# Sheet1.net
KiCad netlist of a schematic drawn in Altium Designer
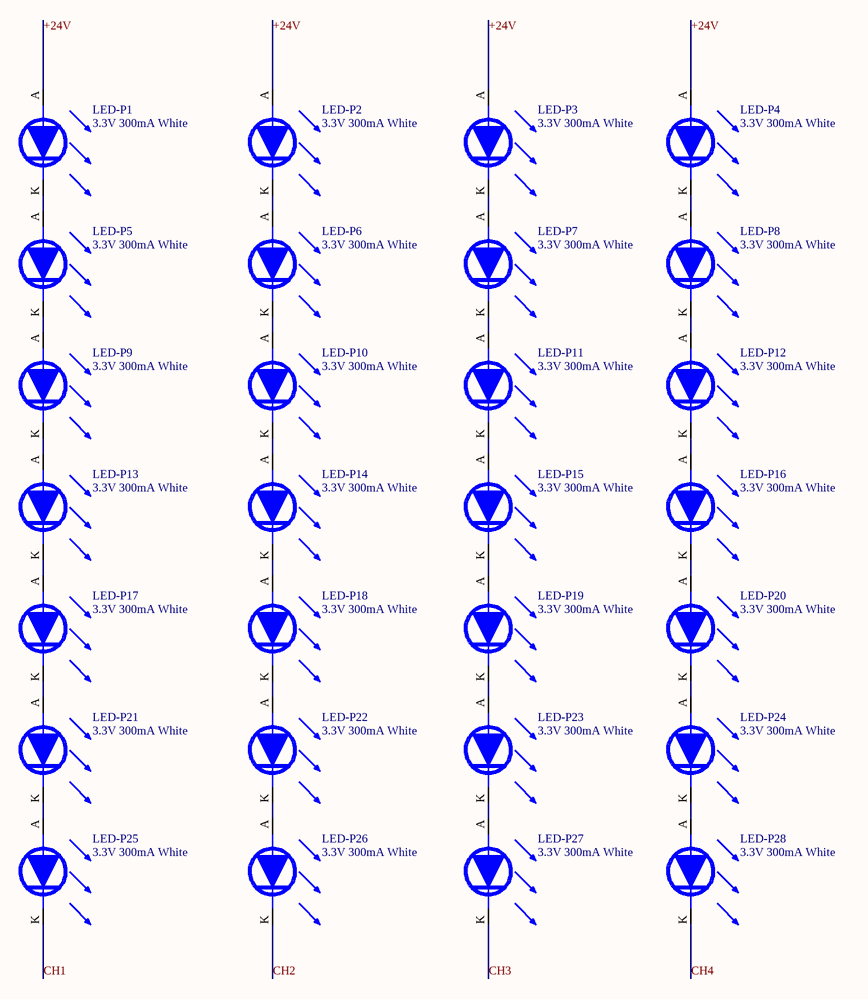
[diagram p0: Sheet1.SchDoc]

(export (version "E")
  (design (tool "Eeschema 10.0.6"))
  (components
    (comp (ref "LED-P1")
      (value "3.3V 300mA White")
      (footprint "PCBComponent_1")
      (description "High power 1W light emitting diode White")
      (libsource (lib "Integrated_Library1") (part "LED white P1"))
    )
    (comp (ref "LED-P2")
      (value "3.3V 300mA White")
      (footprint "PCBComponent_1")
      (description "High power 1W light emitting diode White")
      (libsource (lib "Integrated_Library1") (part "LED white P1"))
    )
    (comp (ref "LED-P3")
      (value "3.3V 300mA White")
      (footprint "PCBComponent_1")
      (description "High power 1W light emitting diode White")
      (libsource (lib "Integrated_Library1") (part "LED white P1"))
    )
    (comp (ref "LED-P4")
      (value "3.3V 300mA White")
      (footprint "PCBComponent_1")
      (description "High power 1W light emitting diode White")
      (libsource (lib "Integrated_Library1") (part "LED white P1"))
    )
    (comp (ref "LED-P5")
      (value "3.3V 300mA White")
      (footprint "PCBComponent_1")
      (description "High power 1W light emitting diode White")
      (libsource (lib "Integrated_Library1") (part "LED white P1"))
    )
    (comp (ref "LED-P6")
      (value "3.3V 300mA White")
      (footprint "PCBComponent_1")
      (description "High power 1W light emitting diode White")
      (libsource (lib "Integrated_Library1") (part "LED white P1"))
    )
    (comp (ref "LED-P7")
      (value "3.3V 300mA White")
      (footprint "PCBComponent_1")
      (description "High power 1W light emitting diode White")
      (libsource (lib "Integrated_Library1") (part "LED white P1"))
    )
    (comp (ref "LED-P8")
      (value "3.3V 300mA White")
      (footprint "PCBComponent_1")
      (description "High power 1W light emitting diode White")
      (libsource (lib "Integrated_Library1") (part "LED white P1"))
    )
    (comp (ref "LED-P9")
      (value "3.3V 300mA White")
      (footprint "PCBComponent_1")
      (description "High power 1W light emitting diode White")
      (libsource (lib "Integrated_Library1") (part "LED white P1"))
    )
    (comp (ref "LED-P10")
      (value "3.3V 300mA White")
      (footprint "PCBComponent_1")
      (description "High power 1W light emitting diode White")
      (libsource (lib "Integrated_Library1") (part "LED white P1"))
    )
    (comp (ref "LED-P11")
      (value "3.3V 300mA White")
      (footprint "PCBComponent_1")
      (description "High power 1W light emitting diode White")
      (libsource (lib "Integrated_Library1") (part "LED white P1"))
    )
    (comp (ref "LED-P12")
      (value "3.3V 300mA White")
      (footprint "PCBComponent_1")
      (description "High power 1W light emitting diode White")
      (libsource (lib "Integrated_Library1") (part "LED white P1"))
    )
    (comp (ref "LED-P13")
      (value "3.3V 300mA White")
      (footprint "PCBComponent_1")
      (description "High power 1W light emitting diode White")
      (libsource (lib "Integrated_Library1") (part "LED white P1"))
    )
    (comp (ref "LED-P14")
      (value "3.3V 300mA White")
      (footprint "PCBComponent_1")
      (description "High power 1W light emitting diode White")
      (libsource (lib "Integrated_Library1") (part "LED white P1"))
    )
    (comp (ref "LED-P15")
      (value "3.3V 300mA White")
      (footprint "PCBComponent_1")
      (description "High power 1W light emitting diode White")
      (libsource (lib "Integrated_Library1") (part "LED white P1"))
    )
    (comp (ref "LED-P16")
      (value "3.3V 300mA White")
      (footprint "PCBComponent_1")
      (description "High power 1W light emitting diode White")
      (libsource (lib "Integrated_Library1") (part "LED white P1"))
    )
    (comp (ref "LED-P17")
      (value "3.3V 300mA White")
      (footprint "PCBComponent_1")
      (description "High power 1W light emitting diode White")
      (libsource (lib "Integrated_Library1") (part "LED white P1"))
    )
    (comp (ref "LED-P18")
      (value "3.3V 300mA White")
      (footprint "PCBComponent_1")
      (description "High power 1W light emitting diode White")
      (libsource (lib "Integrated_Library1") (part "LED white P1"))
    )
    (comp (ref "LED-P19")
      (value "3.3V 300mA White")
      (footprint "PCBComponent_1")
      (description "High power 1W light emitting diode White")
      (libsource (lib "Integrated_Library1") (part "LED white P1"))
    )
    (comp (ref "LED-P20")
      (value "3.3V 300mA White")
      (footprint "PCBComponent_1")
      (description "High power 1W light emitting diode White")
      (libsource (lib "Integrated_Library1") (part "LED white P1"))
    )
    (comp (ref "LED-P21")
      (value "3.3V 300mA White")
      (footprint "PCBComponent_1")
      (description "High power 1W light emitting diode White")
      (libsource (lib "Integrated_Library1") (part "LED white P1"))
    )
    (comp (ref "LED-P22")
      (value "3.3V 300mA White")
      (footprint "PCBComponent_1")
      (description "High power 1W light emitting diode White")
      (libsource (lib "Integrated_Library1") (part "LED white P1"))
    )
    (comp (ref "LED-P23")
      (value "3.3V 300mA White")
      (footprint "PCBComponent_1")
      (description "High power 1W light emitting diode White")
      (libsource (lib "Integrated_Library1") (part "LED white P1"))
    )
    (comp (ref "LED-P24")
      (value "3.3V 300mA White")
      (footprint "PCBComponent_1")
      (description "High power 1W light emitting diode White")
      (libsource (lib "Integrated_Library1") (part "LED white P1"))
    )
    (comp (ref "LED-P25")
      (value "3.3V 300mA White")
      (footprint "PCBComponent_1")
      (description "High power 1W light emitting diode White")
      (libsource (lib "Integrated_Library1") (part "LED white P1"))
    )
    (comp (ref "LED-P26")
      (value "3.3V 300mA White")
      (footprint "PCBComponent_1")
      (description "High power 1W light emitting diode White")
      (libsource (lib "Integrated_Library1") (part "LED white P1"))
    )
    (comp (ref "LED-P27")
      (value "3.3V 300mA White")
      (footprint "PCBComponent_1")
      (description "High power 1W light emitting diode White")
      (libsource (lib "Integrated_Library1") (part "LED white P1"))
    )
    (comp (ref "LED-P28")
      (value "3.3V 300mA White")
      (footprint "PCBComponent_1")
      (description "High power 1W light emitting diode White")
      (libsource (lib "Integrated_Library1") (part "LED white P1"))
    )
  )
  (nets
    (net (code "1") (name "/+24V") (class "Default")
      (node (ref "LED-P1") (pin "A") (pinfunction "A_A") (pintype "passive"))
      (node (ref "LED-P2") (pin "A") (pinfunction "A_A") (pintype "passive"))
      (node (ref "LED-P3") (pin "A") (pinfunction "A_A") (pintype "passive"))
      (node (ref "LED-P4") (pin "A") (pinfunction "A_A") (pintype "passive"))
    )
    (net (code "2") (name "/CH1") (class "Default")
      (node (ref "LED-P25") (pin "K") (pinfunction "K_K") (pintype "passive"))
    )
    (net (code "3") (name "/CH2") (class "Default")
      (node (ref "LED-P26") (pin "K") (pinfunction "K_K") (pintype "passive"))
    )
    (net (code "4") (name "/CH3") (class "Default")
      (node (ref "LED-P27") (pin "K") (pinfunction "K_K") (pintype "passive"))
    )
    (net (code "5") (name "/CH4") (class "Default")
      (node (ref "LED-P28") (pin "K") (pinfunction "K_K") (pintype "passive"))
    )
    (net (code "6") (name "Net-(LED-P1-PadK)") (class "Default")
      (node (ref "LED-P1") (pin "K") (pinfunction "K_K") (pintype "passive"))
      (node (ref "LED-P5") (pin "A") (pinfunction "A_A") (pintype "passive"))
    )
    (net (code "7") (name "Net-(LED-P2-PadK)") (class "Default")
      (node (ref "LED-P2") (pin "K") (pinfunction "K_K") (pintype "passive"))
      (node (ref "LED-P6") (pin "A") (pinfunction "A_A") (pintype "passive"))
    )
    (net (code "8") (name "Net-(LED-P3-PadK)") (class "Default")
      (node (ref "LED-P3") (pin "K") (pinfunction "K_K") (pintype "passive"))
      (node (ref "LED-P7") (pin "A") (pinfunction "A_A") (pintype "passive"))
    )
    (net (code "9") (name "Net-(LED-P4-PadK)") (class "Default")
      (node (ref "LED-P4") (pin "K") (pinfunction "K_K") (pintype "passive"))
      (node (ref "LED-P8") (pin "A") (pinfunction "A_A") (pintype "passive"))
    )
    (net (code "10") (name "Net-(LED-P5-PadK)") (class "Default")
      (node (ref "LED-P5") (pin "K") (pinfunction "K_K") (pintype "passive"))
      (node (ref "LED-P9") (pin "A") (pinfunction "A_A") (pintype "passive"))
    )
    (net (code "11") (name "Net-(LED-P10-PadA)") (class "Default")
      (node (ref "LED-P10") (pin "A") (pinfunction "A_A") (pintype "passive"))
      (node (ref "LED-P6") (pin "K") (pinfunction "K_K") (pintype "passive"))
    )
    (net (code "12") (name "Net-(LED-P10-PadK)") (class "Default")
      (node (ref "LED-P10") (pin "K") (pinfunction "K_K") (pintype "passive"))
      (node (ref "LED-P14") (pin "A") (pinfunction "A_A") (pintype "passive"))
    )
    (net (code "13") (name "Net-(LED-P11-PadA)") (class "Default")
      (node (ref "LED-P11") (pin "A") (pinfunction "A_A") (pintype "passive"))
      (node (ref "LED-P7") (pin "K") (pinfunction "K_K") (pintype "passive"))
    )
    (net (code "14") (name "Net-(LED-P11-PadK)") (class "Default")
      (node (ref "LED-P11") (pin "K") (pinfunction "K_K") (pintype "passive"))
      (node (ref "LED-P15") (pin "A") (pinfunction "A_A") (pintype "passive"))
    )
    (net (code "15") (name "Net-(LED-P12-PadA)") (class "Default")
      (node (ref "LED-P12") (pin "A") (pinfunction "A_A") (pintype "passive"))
      (node (ref "LED-P8") (pin "K") (pinfunction "K_K") (pintype "passive"))
    )
    (net (code "16") (name "Net-(LED-P12-PadK)") (class "Default")
      (node (ref "LED-P12") (pin "K") (pinfunction "K_K") (pintype "passive"))
      (node (ref "LED-P16") (pin "A") (pinfunction "A_A") (pintype "passive"))
    )
    (net (code "17") (name "Net-(LED-P13-PadA)") (class "Default")
      (node (ref "LED-P13") (pin "A") (pinfunction "A_A") (pintype "passive"))
      (node (ref "LED-P9") (pin "K") (pinfunction "K_K") (pintype "passive"))
    )
    (net (code "18") (name "Net-(LED-P13-PadK)") (class "Default")
      (node (ref "LED-P13") (pin "K") (pinfunction "K_K") (pintype "passive"))
      (node (ref "LED-P17") (pin "A") (pinfunction "A_A") (pintype "passive"))
    )
    (net (code "19") (name "Net-(LED-P14-PadK)") (class "Default")
      (node (ref "LED-P14") (pin "K") (pinfunction "K_K") (pintype "passive"))
      (node (ref "LED-P18") (pin "A") (pinfunction "A_A") (pintype "passive"))
    )
    (net (code "20") (name "Net-(LED-P15-PadK)") (class "Default")
      (node (ref "LED-P15") (pin "K") (pinfunction "K_K") (pintype "passive"))
      (node (ref "LED-P19") (pin "A") (pinfunction "A_A") (pintype "passive"))
    )
    (net (code "21") (name "Net-(LED-P16-PadK)") (class "Default")
      (node (ref "LED-P16") (pin "K") (pinfunction "K_K") (pintype "passive"))
      (node (ref "LED-P20") (pin "A") (pinfunction "A_A") (pintype "passive"))
    )
    (net (code "22") (name "Net-(LED-P17-PadK)") (class "Default")
      (node (ref "LED-P17") (pin "K") (pinfunction "K_K") (pintype "passive"))
      (node (ref "LED-P21") (pin "A") (pinfunction "A_A") (pintype "passive"))
    )
    (net (code "23") (name "Net-(LED-P18-PadK)") (class "Default")
      (node (ref "LED-P18") (pin "K") (pinfunction "K_K") (pintype "passive"))
      (node (ref "LED-P22") (pin "A") (pinfunction "A_A") (pintype "passive"))
    )
    (net (code "24") (name "Net-(LED-P19-PadK)") (class "Default")
      (node (ref "LED-P19") (pin "K") (pinfunction "K_K") (pintype "passive"))
      (node (ref "LED-P23") (pin "A") (pinfunction "A_A") (pintype "passive"))
    )
    (net (code "25") (name "Net-(LED-P20-PadK)") (class "Default")
      (node (ref "LED-P20") (pin "K") (pinfunction "K_K") (pintype "passive"))
      (node (ref "LED-P24") (pin "A") (pinfunction "A_A") (pintype "passive"))
    )
    (net (code "26") (name "Net-(LED-P21-PadK)") (class "Default")
      (node (ref "LED-P21") (pin "K") (pinfunction "K_K") (pintype "passive"))
      (node (ref "LED-P25") (pin "A") (pinfunction "A_A") (pintype "passive"))
    )
    (net (code "27") (name "Net-(LED-P22-PadK)") (class "Default")
      (node (ref "LED-P22") (pin "K") (pinfunction "K_K") (pintype "passive"))
      (node (ref "LED-P26") (pin "A") (pinfunction "A_A") (pintype "passive"))
    )
    (net (code "28") (name "Net-(LED-P23-PadK)") (class "Default")
      (node (ref "LED-P23") (pin "K") (pinfunction "K_K") (pintype "passive"))
      (node (ref "LED-P27") (pin "A") (pinfunction "A_A") (pintype "passive"))
    )
    (net (code "29") (name "Net-(LED-P24-PadK)") (class "Default")
      (node (ref "LED-P24") (pin "K") (pinfunction "K_K") (pintype "passive"))
      (node (ref "LED-P28") (pin "A") (pinfunction "A_A") (pintype "passive"))
    )
  )
)
